# FanControl.net
KiCad netlist of a schematic drawn in Altium Designer
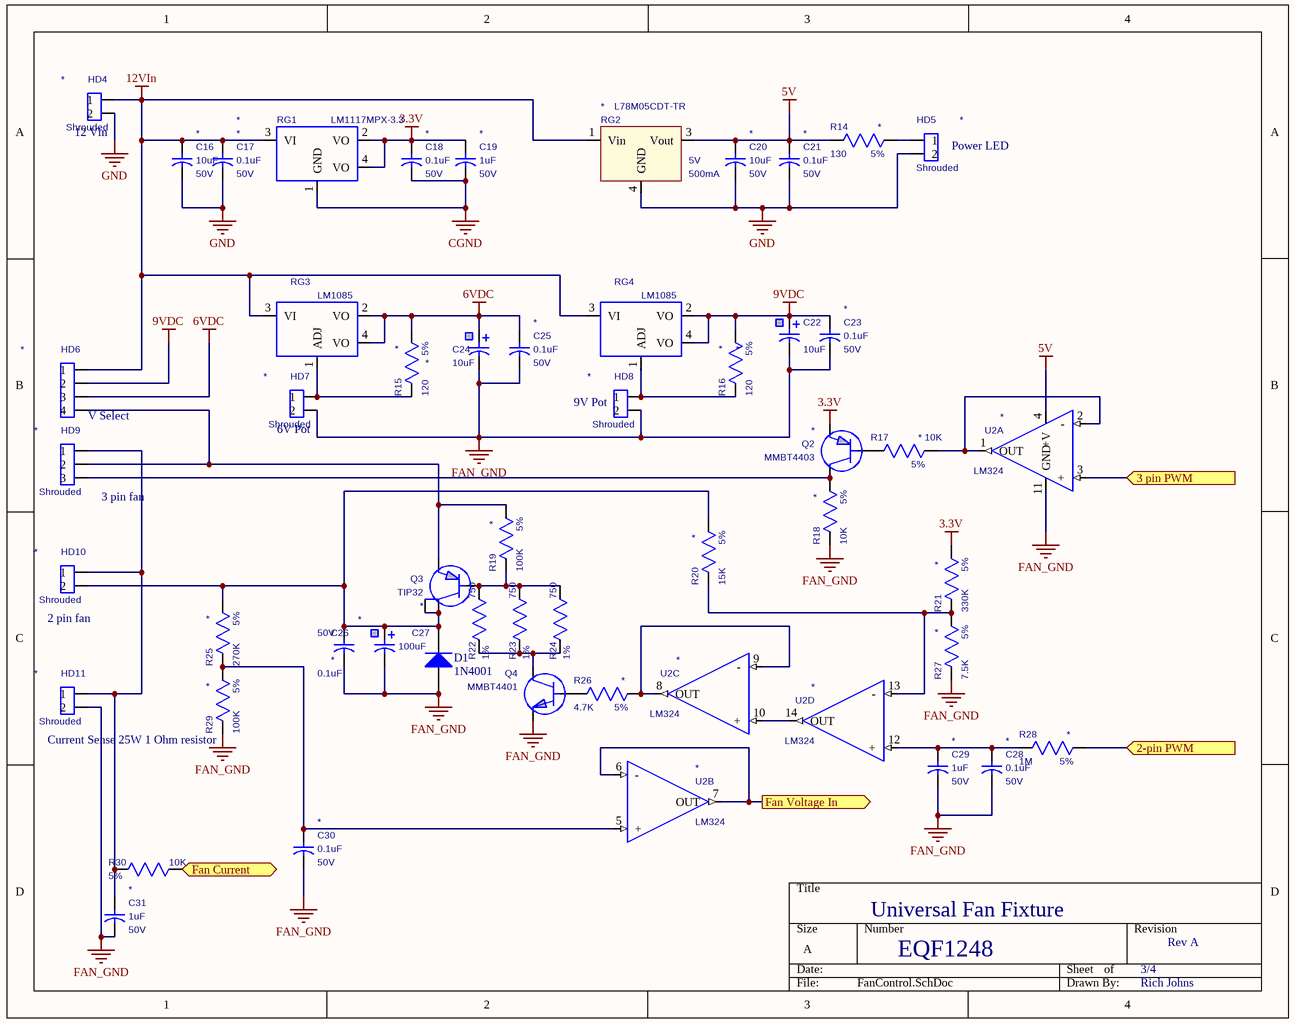
[diagram p0: FanControl.SchDoc]

(export (version "E")
  (design (tool "Eeschema 10.0.6"))
  (components
    (comp (ref "C16")
      (value "10uF")
      (footprint "1206")
      (fields
        (field (name "DNS") "*")
        (field (name "VOLTAGE") "50V")
        (field (name "TOLERANCE") "+/- 20%")
        (field (name "Comment") "CAP_NON_POLAR_SMT")
        (field (name "CHECKEDBY") "Sam Rhoufiry")
        (field (name "CREATEDBY") "Mike Tyger")
        (field (name "LASTUPDATEDBY") "Mike Tyger")
      )
      (libsource (lib "bome") (part "CAP_NON_POLAR_SMT"))
    )
    (comp (ref "C17")
      (value "0.1uF")
      (footprint "0603")
      (fields
        (field (name "DNS") "*")
        (field (name "VOLTAGE") "50V")
        (field (name "TOLERANCE") "+/- 20%")
        (field (name "Comment") "CAP_NON_POLAR_SMT")
        (field (name "CHECKEDBY") "Sam Rhoufiry")
        (field (name "CREATEDBY") "Mike Tyger")
        (field (name "LASTUPDATEDBY") "Mike Tyger")
      )
      (libsource (lib "bome") (part "CAP_NON_POLAR_SMT"))
    )
    (comp (ref "C18")
      (value "0.1uF")
      (footprint "0603")
      (fields
        (field (name "DNS") "*")
        (field (name "VOLTAGE") "50V")
        (field (name "TOLERANCE") "+/- 20%")
        (field (name "Comment") "CAP_NON_POLAR_SMT")
        (field (name "CHECKEDBY") "Sam Rhoufiry")
        (field (name "CREATEDBY") "Mike Tyger")
        (field (name "LASTUPDATEDBY") "Mike Tyger")
      )
      (libsource (lib "bome") (part "CAP_NON_POLAR_SMT"))
    )
    (comp (ref "C19")
      (value "1uF")
      (footprint "1812")
      (description "Capacitor, 1uF, 50V, Ceramic, Z5U, +/- 20%, Non-Polar, 1812, Kemet: C1812C105M5UACTU or equivalent")
      (fields
        (field (name "DNS") "*")
        (field (name "VOLTAGE") "50V")
        (field (name "TOLERANCE") "+/- 20%")
        (field (name "Comment") "CAP_NON_POLAR_SMT")
        (field (name "CHECKEDBY") "Sam Rhoufiry")
        (field (name "CREATEDBY") "Mike Tyger")
        (field (name "LASTUPDATEDBY") "Mike Tyger")
      )
      (libsource (lib "bome") (part "CAP_NON_POLAR_SMT"))
    )
    (comp (ref "C20")
      (value "10uF")
      (footprint "1206")
      (fields
        (field (name "DNS") "*")
        (field (name "VOLTAGE") "50V")
        (field (name "TOLERANCE") "+/- 20%")
        (field (name "Comment") "CAP_NON_POLAR_SMT")
        (field (name "CHECKEDBY") "Sam Rhoufiry")
        (field (name "CREATEDBY") "Mike Tyger")
        (field (name "LASTUPDATEDBY") "Mike Tyger")
      )
      (libsource (lib "bome") (part "CAP_NON_POLAR_SMT"))
    )
    (comp (ref "C21")
      (value "0.1uF")
      (footprint "0603")
      (fields
        (field (name "DNS") "*")
        (field (name "VOLTAGE") "50V")
        (field (name "TOLERANCE") "+/- 20%")
        (field (name "Comment") "CAP_NON_POLAR_SMT")
        (field (name "CHECKEDBY") "Sam Rhoufiry")
        (field (name "CREATEDBY") "Mike Tyger")
        (field (name "LASTUPDATEDBY") "Mike Tyger")
      )
      (libsource (lib "bome") (part "CAP_NON_POLAR_SMT"))
    )
    (comp (ref "C22")
      (value "10uF")
      (footprint "EIA3216-18")
      (fields
        (field (name "VOLTAGE") "16V")
        (field (name "TOLERANCE") "+/- 20%")
        (field (name "DNS") "*")
        (field (name "Comment") "10UF_TANT_16V")
        (field (name "CHECKEDBY") "B. Lyon")
      )
      (libsource (lib "bome") (part "10UF_TANT_16V"))
    )
    (comp (ref "C23")
      (value "0.1uF")
      (footprint "0603")
      (fields
        (field (name "DNS") "*")
        (field (name "VOLTAGE") "50V")
        (field (name "TOLERANCE") "+/- 20%")
        (field (name "Comment") "CAP_NON_POLAR_SMT")
        (field (name "CHECKEDBY") "Sam Rhoufiry")
        (field (name "CREATEDBY") "Mike Tyger")
        (field (name "LASTUPDATEDBY") "Mike Tyger")
      )
      (libsource (lib "bome") (part "CAP_NON_POLAR_SMT"))
    )
    (comp (ref "C24")
      (value "10uF")
      (footprint "EIA3216-18")
      (fields
        (field (name "VOLTAGE") "16V")
        (field (name "TOLERANCE") "+/- 20%")
        (field (name "DNS") "*")
        (field (name "Comment") "10UF_TANT_16V")
        (field (name "CHECKEDBY") "B. Lyon")
      )
      (libsource (lib "bome") (part "10UF_TANT_16V"))
    )
    (comp (ref "C25")
      (value "0.1uF")
      (footprint "0603")
      (fields
        (field (name "DNS") "*")
        (field (name "VOLTAGE") "50V")
        (field (name "TOLERANCE") "+/- 20%")
        (field (name "Comment") "CAP_NON_POLAR_SMT")
        (field (name "CHECKEDBY") "Sam Rhoufiry")
        (field (name "CREATEDBY") "Mike Tyger")
        (field (name "LASTUPDATEDBY") "Mike Tyger")
      )
      (libsource (lib "bome") (part "CAP_NON_POLAR_SMT"))
    )
    (comp (ref "C26")
      (value "100uF")
      (footprint "CAP_100RP42")
      (fields
        (field (name "DNS") "*")
        (field (name "VOLTAGE") "35V")
        (field (name "TOLERANCE") "+/- 20%")
        (field (name "Comment") "100UF_RP_35V_100")
        (field (name "CHECKEDBY") "A. Tyger")
      )
      (libsource (lib "bome") (part "100UF_RP_35V_100"))
    )
    (comp (ref "C27")
      (value "0.1uF")
      (footprint "0603")
      (fields
        (field (name "DNS") "*")
        (field (name "VOLTAGE") "50V")
        (field (name "TOLERANCE") "+/- 20%")
        (field (name "Comment") "CAP_NON_POLAR_SMT")
        (field (name "CHECKEDBY") "Sam Rhoufiry")
        (field (name "CREATEDBY") "Mike Tyger")
        (field (name "LASTUPDATEDBY") "Mike Tyger")
      )
      (libsource (lib "bome") (part "CAP_NON_POLAR_SMT"))
    )
    (comp (ref "C28")
      (value "0.1uF")
      (footprint "0603")
      (fields
        (field (name "DNS") "*")
        (field (name "VOLTAGE") "50V")
        (field (name "TOLERANCE") "+/- 20%")
        (field (name "Comment") "CAP_NON_POLAR_SMT")
        (field (name "CHECKEDBY") "Sam Rhoufiry")
        (field (name "CREATEDBY") "Mike Tyger")
        (field (name "LASTUPDATEDBY") "Mike Tyger")
      )
      (libsource (lib "bome") (part "CAP_NON_POLAR_SMT"))
    )
    (comp (ref "C29")
      (value "1uF")
      (footprint "0603")
      (fields
        (field (name "DNS") "*")
        (field (name "VOLTAGE") "50V")
        (field (name "TOLERANCE") "+/- 20%")
        (field (name "Comment") "CAP_NON_POLAR_SMT")
        (field (name "CHECKEDBY") "Sam Rhoufiry")
        (field (name "CREATEDBY") "Mike Tyger")
        (field (name "LASTUPDATEDBY") "Mike Tyger")
      )
      (libsource (lib "bome") (part "CAP_NON_POLAR_SMT"))
    )
    (comp (ref "C30")
      (value "0.1uF")
      (footprint "0603")
      (fields
        (field (name "DNS") "*")
        (field (name "VOLTAGE") "50V")
        (field (name "TOLERANCE") "+/- 20%")
        (field (name "Comment") "CAP_NON_POLAR_SMT")
        (field (name "CHECKEDBY") "Sam Rhoufiry")
        (field (name "CREATEDBY") "Mike Tyger")
        (field (name "LASTUPDATEDBY") "Mike Tyger")
      )
      (libsource (lib "bome") (part "CAP_NON_POLAR_SMT"))
    )
    (comp (ref "C31")
      (value "1uF")
      (footprint "0603")
      (fields
        (field (name "DNS") "*")
        (field (name "VOLTAGE") "50V")
        (field (name "TOLERANCE") "+/- 20%")
        (field (name "Comment") "CAP_NON_POLAR_SMT")
        (field (name "CHECKEDBY") "Sam Rhoufiry")
        (field (name "CREATEDBY") "Mike Tyger")
        (field (name "LASTUPDATEDBY") "Mike Tyger")
      )
      (libsource (lib "bome") (part "CAP_NON_POLAR_SMT"))
    )
    (comp (ref "D1")
      (value "1N4001")
      (footprint "DSO-C2/X3.3")
      (description "Default Diode")
      (fields (field (name "PUBLISHER") "Altium Limited"))
      (libsource (lib "Miscellaneous Devices") (part "Diode"))
    )
    (comp (ref "HD4")
      (value "HDR2PIN100SHRD")
      (footprint "HDR2PIN100SHRD")
      (description "Header, 0.100 in., 2 Pins, Shrouded, AMP: 644486-2")
      (fields
        (field (name "DNS") "*")
        (field (name "HEADERTYPE") "Shrouded")
        (field (name "CHECKEDBY") "*")
        (field (name "LASTUPDATEDBY") "Mike Tyger")
      )
      (libsource (lib "bome") (part "HDR2PIN100SHRD"))
    )
    (comp (ref "HD5")
      (value "HDR2PIN100SHRD")
      (footprint "HDR2PIN100SHRD")
      (description "Header, 0.100 in., 2 Pins, Shrouded, AMP: 644486-2")
      (fields
        (field (name "DNS") "*")
        (field (name "HEADERTYPE") "Shrouded")
        (field (name "CHECKEDBY") "*")
        (field (name "LASTUPDATEDBY") "Mike Tyger")
      )
      (libsource (lib "bome") (part "HDR2PIN100SHRD"))
    )
    (comp (ref "HD6")
      (value "HDR4PIN100SHRD")
      (footprint "HDR4PIN100SHRD")
      (description "Header, 0.100 in., 4 pin Pins, Shrouded, AMP: 644486-4")
      (fields (field (name "DNS") "*") (field (name "CHECKEDBY") "Michael Angeli"))
      (libsource (lib "bome") (part "HDR4PIN100SHRD"))
    )
    (comp (ref "HD7")
      (value "HDR2PIN100SHRD")
      (footprint "HDR2PIN100SHRD")
      (description "Header, 0.100 in., 2 Pins, Shrouded, AMP: 644486-2")
      (fields
        (field (name "DNS") "*")
        (field (name "HEADERTYPE") "Shrouded")
        (field (name "CHECKEDBY") "*")
        (field (name "LASTUPDATEDBY") "Mike Tyger")
      )
      (libsource (lib "bome") (part "HDR2PIN100SHRD"))
    )
    (comp (ref "HD8")
      (value "HDR2PIN100SHRD")
      (footprint "HDR2PIN100SHRD")
      (description "Header, 0.100 in., 2 Pins, Shrouded, AMP: 644486-2")
      (fields
        (field (name "DNS") "*")
        (field (name "HEADERTYPE") "Shrouded")
        (field (name "CHECKEDBY") "*")
        (field (name "LASTUPDATEDBY") "Mike Tyger")
      )
      (libsource (lib "bome") (part "HDR2PIN100SHRD"))
    )
    (comp (ref "HD9")
      (value "HDR3PIN100SHRD")
      (footprint "HDR3PIN100SHRD")
      (description "Header, 0.100 in., 3 pin Pins, Shrouded, AMP: 644486-3")
      (fields
        (field (name "DNS") "*")
        (field (name "HEADERTYPE") "Shrouded")
        (field (name "CHECKEDBY") "Grunt Mcfunkwhistle")
      )
      (libsource (lib "bome") (part "HDR3PIN100SHRD"))
    )
    (comp (ref "HD10")
      (value "HDR2PIN100SHRD")
      (footprint "HDR2PIN100SHRD")
      (description "Header, 0.100 in., 2 Pins, Shrouded, AMP: 644486-2")
      (fields
        (field (name "DNS") "*")
        (field (name "HEADERTYPE") "Shrouded")
        (field (name "CHECKEDBY") "*")
        (field (name "LASTUPDATEDBY") "Mike Tyger")
      )
      (libsource (lib "bome") (part "HDR2PIN100SHRD"))
    )
    (comp (ref "HD11")
      (value "HDR2PIN100SHRD")
      (footprint "HDR2PIN100SHRD")
      (description "Header, 0.100 in., 2 Pins, Shrouded, AMP: 644486-2")
      (fields
        (field (name "DNS") "*")
        (field (name "HEADERTYPE") "Shrouded")
        (field (name "CHECKEDBY") "*")
        (field (name "LASTUPDATEDBY") "Mike Tyger")
      )
      (libsource (lib "bome") (part "HDR2PIN100SHRD"))
    )
    (comp (ref "Q2")
      (value "MMBT4403")
      (footprint "SOT23-3")
      (description "Transistor, MMBT4403, 40V, SOT23-3, PNP, Transistor, On Semi: MMBT4403LT1")
      (fields
        (field (name "DNS") "*")
        (field (name "VOLTAGE") "40V")
        (field (name "Comment") "PNP_TRANSISTOR")
        (field (name "CHECKEDBY") "gdeguzman")
        (field (name "LASTUPDATEDBY") "Mike Tyger")
      )
      (libsource (lib "bome") (part "PNP_TRANSISTOR"))
    )
    (comp (ref "Q3")
      (value "TIP32")
      (footprint "TO-220-NORMAL")
      (description "Transistor, TIP32, 40V, TO-220, 3A, PNP, Any")
      (fields (field (name "VOLTAGE") "40V") (field (name "DNS") "*") (field (name "CHECKEDBY") "B. Lyon"))
      (libsource (lib "bome") (part "TIP32"))
    )
    (comp (ref "Q4")
      (value "MMBT4401")
      (footprint "SOT23-3")
      (description "Transistor, MMBT4401, 40V, SOT23, 500mA, 3, NPN, Transistor, On Semi: MMBT4401LT1")
      (fields
        (field (name "VOLTAGE") "40V")
        (field (name "Comment") "2N4401_SOT23")
        (field (name "CHECKEDBY") "gdeguzman")
        (field (name "LASTUPDATEDBY") "Mike Tyger")
      )
      (libsource (lib "bome") (part "2N4401_SOT23"))
    )
    (comp (ref "R14")
      (value "130")
      (footprint "RC0603REFLOW-IPC")
      (description "Resistor, 130, ThickFilm, 5%, 0603, 1/10W, Any")
      (fields
        (field (name "DNS") "*")
        (field (name "TOLERANCE") "5%")
        (field (name "Comment") "R0603REFLOW_5%")
        (field (name "CHECKEDBY") "Michael Angeli")
      )
      (libsource (lib "bome") (part "R0603REFLOW_5%"))
    )
    (comp (ref "R15")
      (value "120")
      (footprint "RC0603REFLOW-IPC")
      (description "Resistor, 120, ThickFilm, 5%, 0603, 1/10W, Any")
      (fields
        (field (name "DNS") "*")
        (field (name "TOLERANCE") "5%")
        (field (name "Comment") "R0603REFLOW_5%")
        (field (name "CHECKEDBY") "Michael Angeli")
      )
      (libsource (lib "bome") (part "R0603REFLOW_5%"))
    )
    (comp (ref "R16")
      (value "120")
      (footprint "RC0603REFLOW-IPC")
      (description "Resistor, 120, ThickFilm, 5%, 0603, 1/10W, Any")
      (fields
        (field (name "DNS") "*")
        (field (name "TOLERANCE") "5%")
        (field (name "Comment") "R0603REFLOW_5%")
        (field (name "CHECKEDBY") "Michael Angeli")
      )
      (libsource (lib "bome") (part "R0603REFLOW_5%"))
    )
    (comp (ref "R17")
      (value "10K")
      (footprint "RC0603REFLOW-IPC")
      (description "Resistor, 10K, ThickFilm, 5%, 0603, 1/10W, Any")
      (fields
        (field (name "DNS") "*")
        (field (name "TOLERANCE") "5%")
        (field (name "Comment") "R0603REFLOW_5%")
        (field (name "CHECKEDBY") "Michael Angeli")
      )
      (libsource (lib "bome") (part "R0603REFLOW_5%"))
    )
    (comp (ref "R18")
      (value "10K")
      (footprint "RC0603REFLOW-IPC")
      (description "Resistor, 10K, ThickFilm, 5%, 0603, 1/10W, Any")
      (fields
        (field (name "DNS") "*")
        (field (name "TOLERANCE") "5%")
        (field (name "Comment") "R0603REFLOW_5%")
        (field (name "CHECKEDBY") "Michael Angeli")
      )
      (libsource (lib "bome") (part "R0603REFLOW_5%"))
    )
    (comp (ref "R19")
      (value "100K")
      (footprint "RC0603REFLOW-IPC")
      (description "Resistor, 100K, ThickFilm, 5%, 0603, 1/10W, Any")
      (fields
        (field (name "DNS") "*")
        (field (name "TOLERANCE") "5%")
        (field (name "Comment") "R0603REFLOW_5%")
        (field (name "CHECKEDBY") "Michael Angeli")
      )
      (libsource (lib "bome") (part "R0603REFLOW_5%"))
    )
    (comp (ref "R20")
      (value "15K")
      (footprint "RC0603REFLOW-IPC")
      (description "Resistor, 15K, ThickFilm, 5%, 0603, 1/10W, Any")
      (fields
        (field (name "DNS") "*")
        (field (name "TOLERANCE") "5%")
        (field (name "Comment") "R0603REFLOW_5%")
        (field (name "CHECKEDBY") "Michael Angeli")
      )
      (libsource (lib "bome") (part "R0603REFLOW_5%"))
    )
    (comp (ref "R21")
      (value "330K")
      (footprint "RC0603REFLOW-IPC")
      (description "Resistor, 330K, ThickFilm, 5%, 0603, 1/10W, Any")
      (fields
        (field (name "DNS") "*")
        (field (name "TOLERANCE") "5%")
        (field (name "Comment") "R0603REFLOW_5%")
        (field (name "CHECKEDBY") "Michael Angeli")
      )
      (libsource (lib "bome") (part "R0603REFLOW_5%"))
    )
    (comp (ref "R22")
      (value "750")
      (footprint "0603")
      (description "Resistor, 750, 1%, 0603, 1/10W, 2, Any")
      (fields
        (field (name "TOLERANCE") "1%")
        (field (name "Comment") "Resistor_0603_1%")
        (field (name "CHECKEDBY") "gdeguzman")
        (field (name "LASTUPDATEDBY") "Ben Hill")
      )
      (libsource (lib "bome") (part "Resistor_0603_1%"))
    )
    (comp (ref "R23")
      (value "750")
      (footprint "0603")
      (description "Resistor, 750, 1%, 0603, 1/10W, 2, Any")
      (fields
        (field (name "TOLERANCE") "1%")
        (field (name "Comment") "Resistor_0603_1%")
        (field (name "CHECKEDBY") "gdeguzman")
        (field (name "LASTUPDATEDBY") "Ben Hill")
      )
      (libsource (lib "bome") (part "Resistor_0603_1%"))
    )
    (comp (ref "R24")
      (value "750")
      (footprint "0603")
      (description "Resistor, 750, 1%, 0603, 1/10W, 2, Any")
      (fields
        (field (name "TOLERANCE") "1%")
        (field (name "Comment") "Resistor_0603_1%")
        (field (name "CHECKEDBY") "gdeguzman")
        (field (name "LASTUPDATEDBY") "Ben Hill")
      )
      (libsource (lib "bome") (part "Resistor_0603_1%"))
    )
    (comp (ref "R25")
      (value "270K")
      (footprint "RC0603REFLOW-IPC")
      (description "Resistor, 270K, ThickFilm, 5%, 0603, 1/10W, Any")
      (fields
        (field (name "DNS") "*")
        (field (name "TOLERANCE") "5%")
        (field (name "Comment") "R0603REFLOW_5%")
        (field (name "CHECKEDBY") "Michael Angeli")
      )
      (libsource (lib "bome") (part "R0603REFLOW_5%"))
    )
    (comp (ref "R26")
      (value "4.7K")
      (footprint "RC0603REFLOW-IPC")
      (description "Resistor, 4.7K, ThickFilm, 5%, 0603, 1/10W, Any")
      (fields
        (field (name "DNS") "*")
        (field (name "TOLERANCE") "5%")
        (field (name "Comment") "R0603REFLOW_5%")
        (field (name "CHECKEDBY") "Michael Angeli")
      )
      (libsource (lib "bome") (part "R0603REFLOW_5%"))
    )
    (comp (ref "R27")
      (value "7.5K")
      (footprint "RC0603REFLOW-IPC")
      (description "Resistor, 7.5K, ThickFilm, 5%, 0603, 1/10W, Any")
      (fields
        (field (name "DNS") "*")
        (field (name "TOLERANCE") "5%")
        (field (name "Comment") "R0603REFLOW_5%")
        (field (name "CHECKEDBY") "Michael Angeli")
      )
      (libsource (lib "bome") (part "R0603REFLOW_5%"))
    )
    (comp (ref "R28")
      (value "1M")
      (footprint "RC0603REFLOW-IPC")
      (description "Resistor, 1M, ThickFilm, 5%, 0603, 1/10W, Any")
      (fields
        (field (name "DNS") "*")
        (field (name "TOLERANCE") "5%")
        (field (name "Comment") "R0603REFLOW_5%")
        (field (name "CHECKEDBY") "Michael Angeli")
      )
      (libsource (lib "bome") (part "R0603REFLOW_5%"))
    )
    (comp (ref "R29")
      (value "100K")
      (footprint "RC0603REFLOW-IPC")
      (description "Resistor, 100K, ThickFilm, 5%, 0603, 1/10W, Any")
      (fields
        (field (name "DNS") "*")
        (field (name "TOLERANCE") "5%")
        (field (name "Comment") "R0603REFLOW_5%")
        (field (name "CHECKEDBY") "Michael Angeli")
      )
      (libsource (lib "bome") (part "R0603REFLOW_5%"))
    )
    (comp (ref "R30")
      (value "10K")
      (footprint "0603")
      (description "Resistor, 10K, ThickFilm, 5%, 0603, 1/10W, 2, Any")
      (fields
        (field (name "TOLERANCE") "5%")
        (field (name "Comment") "Resistor_0603_5%")
        (field (name "CHECKEDBY") "Joe Diffie")
        (field (name "LASTUPDATEDBY") "Rui Zhang")
      )
      (libsource (lib "bome") (part "Resistor_0603_5%"))
    )
    (comp (ref "RG1")
      (value "LM1117MPX-3.3")
      (footprint "SOT-223")
      (description "Regulator, LM1117MPX-3.3, 3.3V, SOT223, 800mA, 4, LDO, National: LM117MPX-3.3")
      (fields
        (field (name "VOLTAGE") "3.3V")
        (field (name "DNS") "*")
        (field (name "Comment") "LM1117SPX-3.3_SOT223")
        (field (name "CHECKEDBY") "gdeguzman")
        (field (name "LASTUPDATEDBY") "Rui Zhang")
      )
      (libsource (lib "bome") (part "LM1117SPX-3.3_SOT223"))
    )
    (comp (ref "RG2")
      (value "L78M05CDT-TR")
      (footprint "DPAK")
      (description "Regulator, L78M05CDT-TR, 5V, DPAK, 500mA, Linear, ST: L78M05CDT-TR or equivalent")
      (fields
        (field (name "VOLTAGE") "5V")
        (field (name "DNS") "*")
        (field (name "AMPERAGE") "500mA")
        (field (name "Comment") "REGULATOR_DPAK")
        (field (name "CHECKEDBY") "B. Lyon")
        (field (name "CREATEDBY") "Mike Tyger")
        (field (name "LASTUPDATEDBY") "Mike Tyger")
      )
      (libsource (lib "bome") (part "REGULATOR_DPAK"))
    )
    (comp (ref "RG3")
      (value "LM1085")
      (footprint "TO-220-NORMAL")
      (description "Regulator, LM1085, Adjustable, TO-220, 3A, LDO, Texas Instruments")
      (fields
        (field (name "VOLTAGE") "Adjustable")
        (field (name "Comment") "LM1085_TO220")
        (field (name "CREATEDBY") "Rui Zhang")
        (field (name "LASTUPDATEDBY") "Rui Zhang")
      )
      (libsource (lib "bome") (part "LM1085_TO220"))
    )
    (comp (ref "RG4")
      (value "LM1085")
      (footprint "TO-220-NORMAL")
      (description "Regulator, LM1085, Adjustable, TO-220, 3A, LDO, Texas Instruments")
      (fields
        (field (name "VOLTAGE") "Adjustable")
        (field (name "Comment") "LM1085_TO220")
        (field (name "CREATEDBY") "Rui Zhang")
        (field (name "LASTUPDATEDBY") "Rui Zhang")
      )
      (libsource (lib "bome") (part "LM1085_TO220"))
    )
    (comp (ref "U2")
      (value "LM324")
      (footprint "SOIC14REFLOW-IPC")
      (description "IC, LM324, SOIC, 14 pin, Op-Amp, National Semiconductor")
      (fields
        (field (name "DNS") "*")
        (field (name "Comment") "LM324_SOIC14")
        (field (name "CHECKEDBY") "B. Lyon")
      )
      (libsource (lib "bome") (part "LM324_SOIC14"))
    )
  )
  (nets
    (net (code "1") (name "/2-pin PWM") (class "Default")
      (node (ref "R28") (pin "1") (pinfunction "pin1_1") (pintype "passive"))
    )
    (net (code "2") (name "/3 pin PWM") (class "Default")
      (node (ref "U2") (pin "3") (pinfunction "+_3") (pintype "input"))
    )
    (net (code "3") (name "/Fan Current") (class "Default")
      (node (ref "R30") (pin "1") (pinfunction "pin1_1") (pintype "passive"))
    )
    (net (code "4") (name "/Fan Voltage In") (class "Default")
      (node (ref "U2") (pin "6") (pinfunction "-_6") (pintype "input"))
      (node (ref "U2") (pin "7") (pinfunction "OUT_7") (pintype "output"))
    )
    (net (code "5") (name "3.3V") (class "Default")
      (node (ref "C18") (pin "1") (pinfunction "pin1_1") (pintype "passive"))
      (node (ref "C19") (pin "1") (pinfunction "pin1_1") (pintype "passive"))
      (node (ref "Q2") (pin "2") (pinfunction "emitter_2") (pintype "passive"))
      (node (ref "R21") (pin "1") (pinfunction "pin1_1") (pintype "passive"))
      (node (ref "RG1") (pin "2") (pinfunction "VO_2") (pintype "passive"))
      (node (ref "RG1") (pin "4") (pinfunction "VO_4") (pintype "passive"))
    )
    (net (code "6") (name "5V") (class "Default")
      (node (ref "C20") (pin "1") (pinfunction "pin1_1") (pintype "passive"))
      (node (ref "C21") (pin "1") (pinfunction "pin1_1") (pintype "passive"))
      (node (ref "R14") (pin "2") (pinfunction "pin2_2") (pintype "passive"))
      (node (ref "RG2") (pin "3") (pinfunction "Vout_3") (pintype "passive"))
      (node (ref "U2") (pin "4") (pinfunction "+V_4") (pintype "power_in"))
    )
    (net (code "7") (name "6VDC") (class "Default")
      (node (ref "C24") (pin "1") (pinfunction "+_1") (pintype "passive"))
      (node (ref "C25") (pin "1") (pinfunction "pin1_1") (pintype "passive"))
      (node (ref "HD6") (pin "3") (pinfunction "3_3") (pintype "passive"))
      (node (ref "R15") (pin "1") (pinfunction "pin1_1") (pintype "passive"))
      (node (ref "RG3") (pin "2") (pinfunction "VO_2") (pintype "passive"))
      (node (ref "RG3") (pin "4") (pinfunction "VO_4") (pintype "passive"))
    )
    (net (code "8") (name "9VDC") (class "Default")
      (node (ref "C22") (pin "1") (pinfunction "+_1") (pintype "passive"))
      (node (ref "C23") (pin "1") (pinfunction "pin1_1") (pintype "passive"))
      (node (ref "HD6") (pin "2") (pinfunction "2_2") (pintype "passive"))
      (node (ref "R16") (pin "1") (pinfunction "pin1_1") (pintype "passive"))
      (node (ref "RG4") (pin "2") (pinfunction "VO_2") (pintype "passive"))
      (node (ref "RG4") (pin "4") (pinfunction "VO_4") (pintype "passive"))
    )
    (net (code "9") (name "12VIn") (class "Default")
      (node (ref "C16") (pin "1") (pinfunction "pin1_1") (pintype "passive"))
      (node (ref "C17") (pin "1") (pinfunction "pin1_1") (pintype "passive"))
      (node (ref "HD4") (pin "1") (pinfunction "1_1") (pintype "passive"))
      (node (ref "HD6") (pin "1") (pinfunction "1_1") (pintype "passive"))
      (node (ref "RG1") (pin "3") (pinfunction "VI_3") (pintype "passive"))
      (node (ref "RG2") (pin "1") (pinfunction "Vin_1") (pintype "passive"))
      (node (ref "RG3") (pin "3") (pinfunction "VI_3") (pintype "passive"))
      (node (ref "RG4") (pin "3") (pinfunction "VI_3") (pintype "passive"))
    )
    (net (code "10") (name "CGND") (class "Default")
      (node (ref "C18") (pin "2") (pinfunction "pin2_2") (pintype "passive"))
      (node (ref "C19") (pin "2") (pinfunction "pin2_2") (pintype "passive"))
      (node (ref "RG1") (pin "1") (pinfunction "GND_1") (pintype "passive"))
    )
    (net (code "11") (name "FAN_GND") (class "Default")
      (node (ref "C22") (pin "2") (pinfunction "-_2") (pintype "passive"))
      (node (ref "C23") (pin "2") (pinfunction "pin2_2") (pintype "passive"))
      (node (ref "C24") (pin "2") (pinfunction "-_2") (pintype "passive"))
      (node (ref "C25") (pin "2") (pinfunction "pin2_2") (pintype "passive"))
      (node (ref "C26") (pin "2") (pinfunction "pin2_2") (pintype "passive"))
      (node (ref "C27") (pin "2") (pinfunction "pin2_2") (pintype "passive"))
      (node (ref "C28") (pin "2") (pinfunction "pin2_2") (pintype "passive"))
      (node (ref "C29") (pin "2") (pinfunction "pin2_2") (pintype "passive"))
      (node (ref "C30") (pin "2") (pinfunction "pin2_2") (pintype "passive"))
      (node (ref "C31") (pin "2") (pinfunction "pin2_2") (pintype "passive"))
      (node (ref "D1") (pin "1") (pinfunction "A_1") (pintype "passive"))
      (node (ref "HD11") (pin "2") (pinfunction "2_2") (pintype "passive"))
      (node (ref "HD7") (pin "2") (pinfunction "2_2") (pintype "passive"))
      (node (ref "HD8") (pin "2") (pinfunction "2_2") (pintype "passive"))
      (node (ref "Q4") (pin "2") (pinfunction "emitter_2") (pintype "passive"))
      (node (ref "R18") (pin "2") (pinfunction "pin2_2") (pintype "passive"))
      (node (ref "R27") (pin "2") (pinfunction "pin2_2") (pintype "passive"))
      (node (ref "R29") (pin "2") (pinfunction "pin2_2") (pintype "passive"))
      (node (ref "U2") (pin "11") (pinfunction "GND_11") (pintype "power_in"))
    )
    (net (code "12") (name "GND") (class "Default")
      (node (ref "C16") (pin "2") (pinfunction "pin2_2") (pintype "passive"))
      (node (ref "C17") (pin "2") (pinfunction "pin2_2") (pintype "passive"))
      (node (ref "C20") (pin "2") (pinfunction "pin2_2") (pintype "passive"))
      (node (ref "C21") (pin "2") (pinfunction "pin2_2") (pintype "passive"))
      (node (ref "HD4") (pin "2") (pinfunction "2_2") (pintype "passive"))
      (node (ref "HD5") (pin "2") (pinfunction "2_2") (pintype "passive"))
      (node (ref "RG2") (pin "4") (pinfunction "GND_4") (pintype "passive"))
    )
    (net (code "13") (name "Net-(C26-pin1)") (class "Default")
      (node (ref "C26") (pin "1") (pinfunction "pin1_1") (pintype "passive"))
      (node (ref "C27") (pin "1") (pinfunction "pin1_1") (pintype "passive"))
      (node (ref "D1") (pin "2") (pinfunction "K_2") (pintype "passive"))
      (node (ref "HD10") (pin "2") (pinfunction "2_2") (pintype "passive"))
      (node (ref "Q3") (pin "2") (pinfunction "C_2") (pintype "passive"))
      (node (ref "Q3") (pin "4") (pinfunction "C_4") (pintype "passive"))
      (node (ref "R20") (pin "1") (pinfunction "pin1_1") (pintype "passive"))
      (node (ref "R25") (pin "1") (pinfunction "pin1_1") (pintype "passive"))
    )
    (net (code "14") (name "Net-(C28-pin1)") (class "Default")
      (node (ref "C28") (pin "1") (pinfunction "pin1_1") (pintype "passive"))
      (node (ref "C29") (pin "1") (pinfunction "pin1_1") (pintype "passive"))
      (node (ref "R28") (pin "2") (pinfunction "pin2_2") (pintype "passive"))
      (node (ref "U2") (pin "12") (pinfunction "+_12") (pintype "input"))
    )
    (net (code "15") (name "Net-(C30-pin1)") (class "Default")
      (node (ref "C30") (pin "1") (pinfunction "pin1_1") (pintype "passive"))
      (node (ref "R25") (pin "2") (pinfunction "pin2_2") (pintype "passive"))
      (node (ref "R29") (pin "1") (pinfunction "pin1_1") (pintype "passive"))
      (node (ref "U2") (pin "5") (pinfunction "+_5") (pintype "input"))
    )
    (net (code "16") (name "Net-(C31-pin1)") (class "Default")
      (node (ref "C31") (pin "1") (pinfunction "pin1_1") (pintype "passive"))
      (node (ref "HD10") (pin "1") (pinfunction "1_1") (pintype "passive"))
      (node (ref "HD11") (pin "1") (pinfunction "1_1") (pintype "passive"))
      (node (ref "HD9") (pin "1") (pinfunction "1_1") (pintype "passive"))
      (node (ref "R30") (pin "2") (pinfunction "pin2_2") (pintype "passive"))
    )
    (net (code "17") (name "Net-(Q2-base)") (class "Default")
      (node (ref "Q2") (pin "1") (pinfunction "base_1") (pintype "passive"))
      (node (ref "R17") (pin "2") (pinfunction "pin2_2") (pintype "passive"))
    )
    (net (code "18") (name "Net-(Q2-collector)") (class "Default")
      (node (ref "HD9") (pin "3") (pinfunction "3_3") (pintype "passive"))
      (node (ref "Q2") (pin "3") (pinfunction "collector_3") (pintype "passive"))
      (node (ref "R18") (pin "1") (pinfunction "pin1_1") (pintype "passive"))
    )
    (net (code "19") (name "Net-(Q3-B)") (class "Default")
      (node (ref "Q3") (pin "1") (pinfunction "B_1") (pintype "passive"))
      (node (ref "R19") (pin "2") (pinfunction "pin2_2") (pintype "passive"))
      (node (ref "R22") (pin "1") (pinfunction "pin1_1") (pintype "passive"))
      (node (ref "R23") (pin "1") (pinfunction "pin1_1") (pintype "passive"))
      (node (ref "R24") (pin "1") (pinfunction "pin1_1") (pintype "passive"))
    )
    (net (code "20") (name "Net-(Q3-E)") (class "Default")
      (node (ref "HD6") (pin "4") (pinfunction "4_4") (pintype "passive"))
      (node (ref "HD9") (pin "2") (pinfunction "2_2") (pintype "passive"))
      (node (ref "Q3") (pin "3") (pinfunction "E_3") (pintype "passive"))
      (node (ref "R19") (pin "1") (pinfunction "pin1_1") (pintype "passive"))
    )
    (net (code "21") (name "Net-(Q4-base)") (class "Default")
      (node (ref "Q4") (pin "1") (pinfunction "base_1") (pintype "passive"))
      (node (ref "R26") (pin "2") (pinfunction "pin2_2") (pintype "passive"))
    )
    (net (code "22") (name "Net-(Q4-collector)") (class "Default")
      (node (ref "Q4") (pin "3") (pinfunction "collector_3") (pintype "passive"))
      (node (ref "R22") (pin "2") (pinfunction "pin2_2") (pintype "passive"))
      (node (ref "R23") (pin "2") (pinfunction "pin2_2") (pintype "passive"))
      (node (ref "R24") (pin "2") (pinfunction "pin2_2") (pintype "passive"))
    )
    (net (code "23") (name "Net-(R14-pin1)") (class "Default")
      (node (ref "HD5") (pin "1") (pinfunction "1_1") (pintype "passive"))
      (node (ref "R14") (pin "1") (pinfunction "pin1_1") (pintype "passive"))
    )
    (net (code "24") (name "Net-(R15-pin2)") (class "Default")
      (node (ref "HD7") (pin "1") (pinfunction "1_1") (pintype "passive"))
      (node (ref "R15") (pin "2") (pinfunction "pin2_2") (pintype "passive"))
      (node (ref "RG3") (pin "1") (pinfunction "ADJ_1") (pintype "passive"))
    )
    (net (code "25") (name "Net-(R16-pin2)") (class "Default")
      (node (ref "HD8") (pin "1") (pinfunction "1_1") (pintype "passive"))
      (node (ref "R16") (pin "2") (pinfunction "pin2_2") (pintype "passive"))
      (node (ref "RG4") (pin "1") (pinfunction "ADJ_1") (pintype "passive"))
    )
    (net (code "26") (name "Net-(R17-pin1)") (class "Default")
      (node (ref "R17") (pin "1") (pinfunction "pin1_1") (pintype "passive"))
      (node (ref "U2") (pin "1") (pinfunction "OUT_1") (pintype "output"))
      (node (ref "U2") (pin "2") (pinfunction "-_2") (pintype "input"))
    )
    (net (code "27") (name "Net-(R20-pin2)") (class "Default")
      (node (ref "R20") (pin "2") (pinfunction "pin2_2") (pintype "passive"))
      (node (ref "R21") (pin "2") (pinfunction "pin2_2") (pintype "passive"))
      (node (ref "R27") (pin "1") (pinfunction "pin1_1") (pintype "passive"))
      (node (ref "U2") (pin "13") (pinfunction "-_13") (pintype "input"))
    )
    (net (code "28") (name "Net-(R26-pin1)") (class "Default")
      (node (ref "R26") (pin "1") (pinfunction "pin1_1") (pintype "passive"))
      (node (ref "U2") (pin "8") (pinfunction "OUT_8") (pintype "output"))
      (node (ref "U2") (pin "9") (pinfunction "-_9") (pintype "input"))
    )
    (net (code "29") (name "Net-(U2C-+)") (class "Default")
      (node (ref "U2") (pin "10") (pinfunction "+_10") (pintype "input"))
      (node (ref "U2") (pin "14") (pinfunction "OUT_14") (pintype "output"))
    )
    (net (code "30") (name "unconnected-(HD4-Pad3)") (class "Default")
      (node (ref "HD4") (pin "3") (pintype "passive"))
    )
    (net (code "31") (name "unconnected-(HD5-Pad3)") (class "Default")
      (node (ref "HD5") (pin "3") (pintype "passive"))
    )
    (net (code "32") (name "unconnected-(HD6-Pad5)") (class "Default")
      (node (ref "HD6") (pin "5") (pintype "passive"))
    )
    (net (code "33") (name "unconnected-(HD7-Pad3)") (class "Default")
      (node (ref "HD7") (pin "3") (pintype "passive"))
    )
    (net (code "34") (name "unconnected-(HD8-Pad3)") (class "Default")
      (node (ref "HD8") (pin "3") (pintype "passive"))
    )
    (net (code "35") (name "unconnected-(HD9-Pad4)") (class "Default")
      (node (ref "HD9") (pin "4") (pintype "passive"))
    )
    (net (code "36") (name "unconnected-(HD10-Pad3)") (class "Default")
      (node (ref "HD10") (pin "3") (pintype "passive"))
    )
    (net (code "37") (name "unconnected-(HD11-Pad3)") (class "Default")
      (node (ref "HD11") (pin "3") (pintype "passive"))
    )
    (net (code "38") (name "unconnected-(RG2-GND-Pad2)") (class "Default")
      (node (ref "RG2") (pin "2") (pinfunction "GND_2") (pintype "passive"))
    )
  )
)
